# BPF_eval_R3.net
KiCad netlist of a schematic drawn in EAGLE
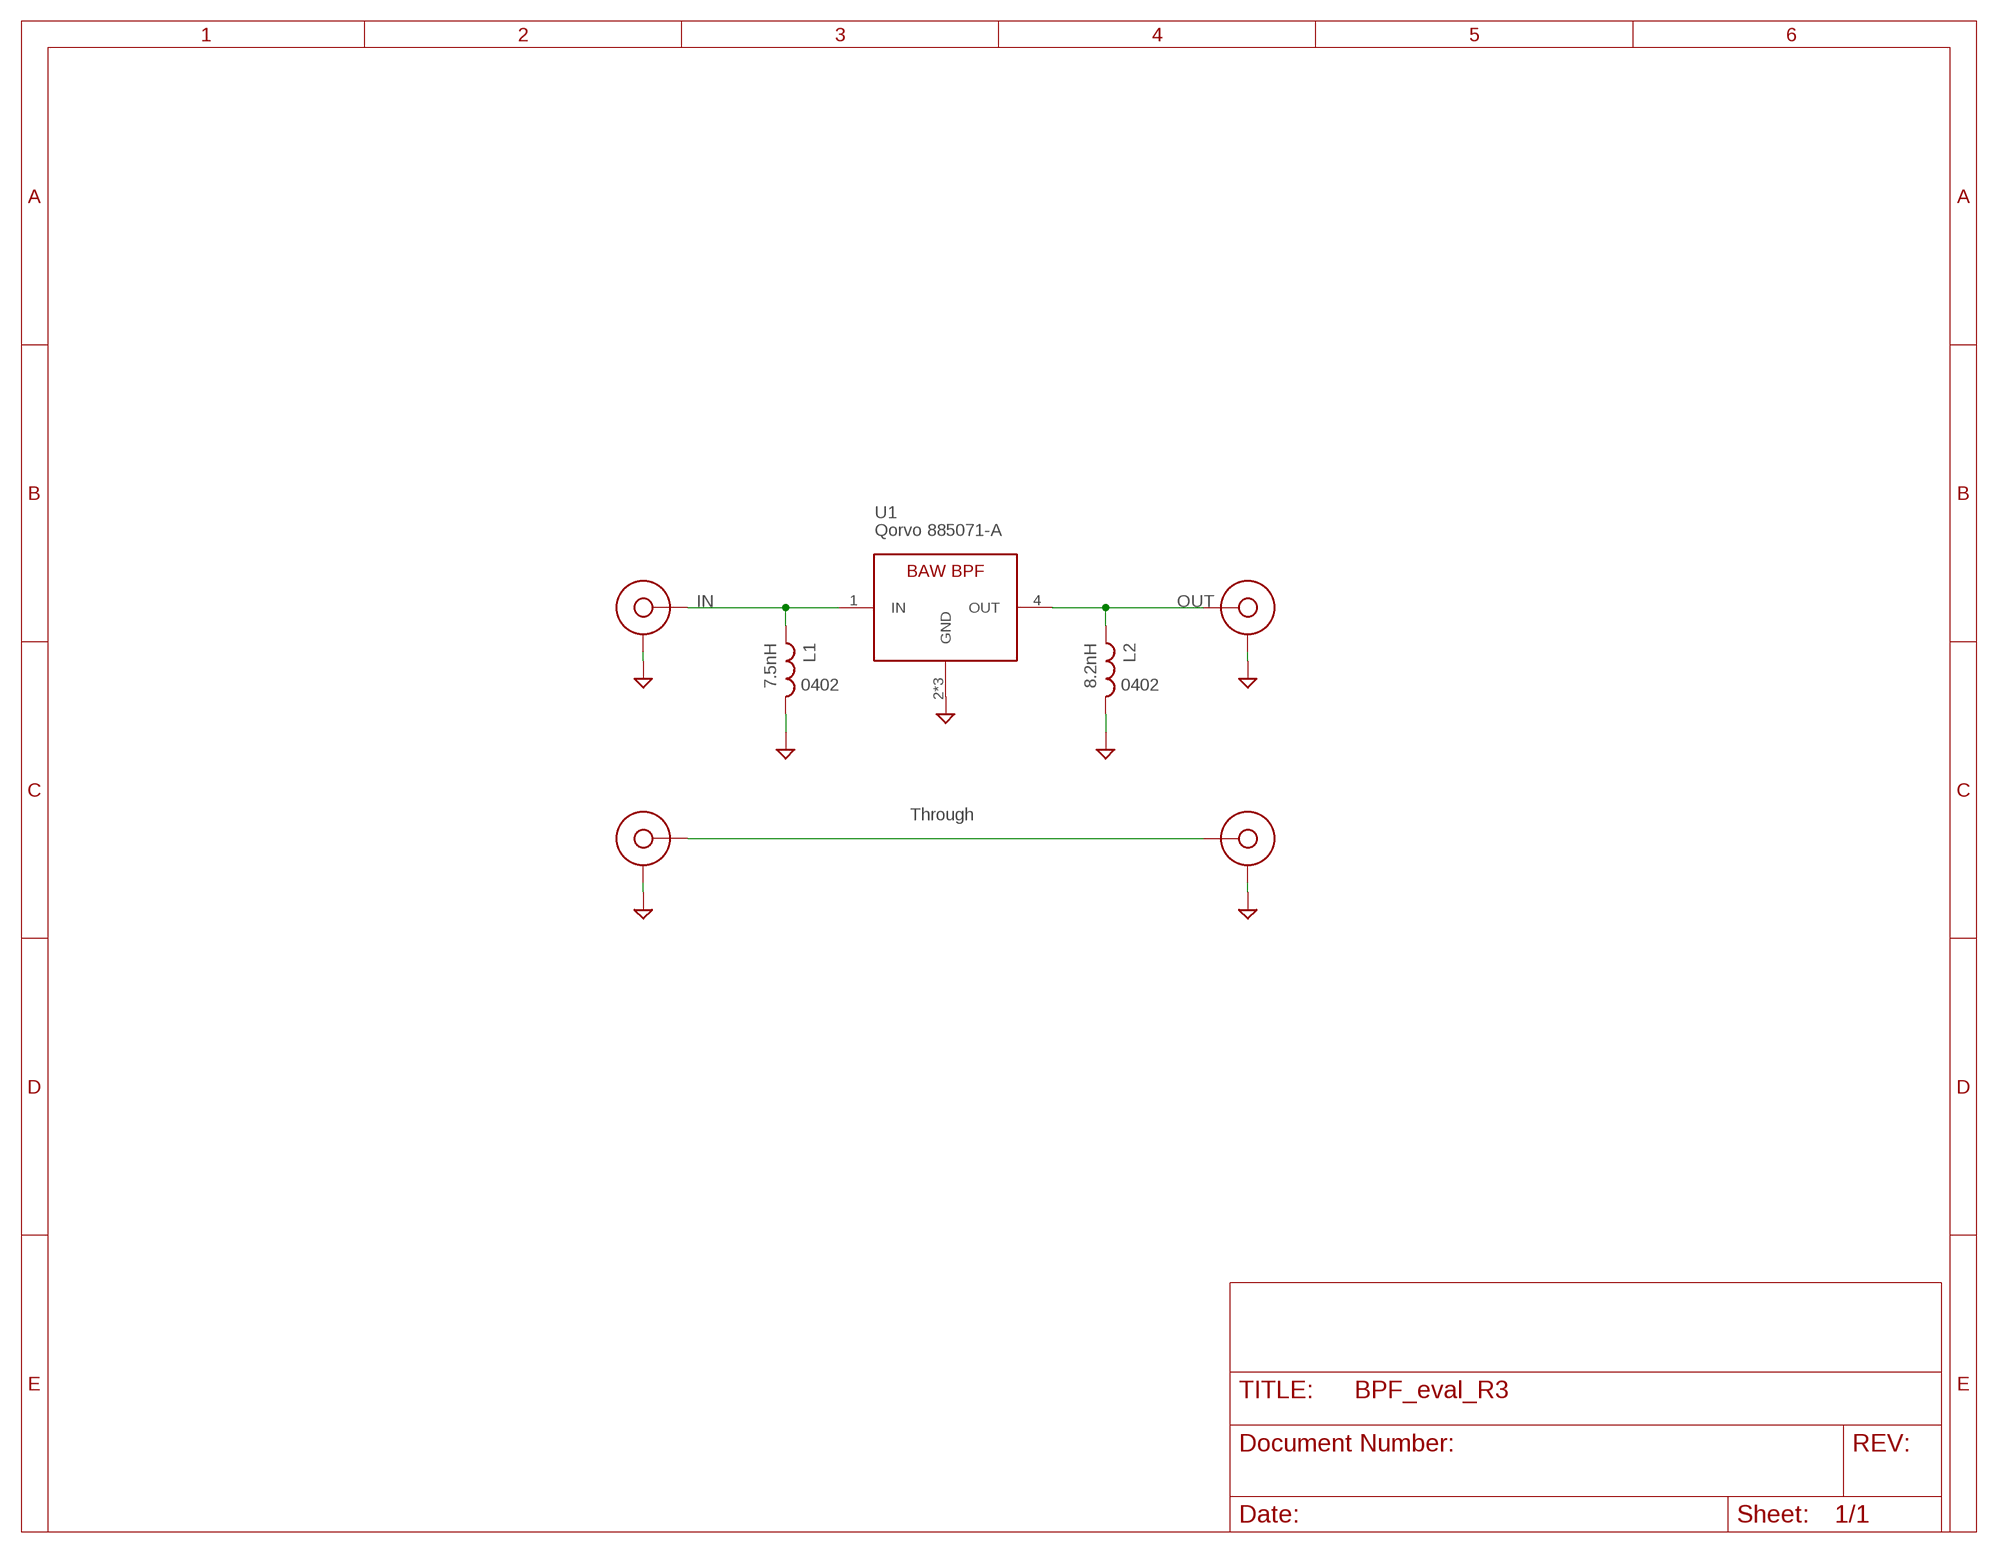
[diagram p0: schematic, sheet 1]

(export (version "E")
  (design (tool "Eeschema 10.0.6"))
  (components
    (comp (ref "CF1")
      (value "SMA-CINCH-END-FIRE")
      (footprint "eagle-import:SMAJ716-ND")
      (libsource (lib "eagle-import") (part "SMA-CINCH-END-FIRE"))
    )
    (comp (ref "CF2")
      (value "SMA-CINCH-END-FIRE")
      (footprint "eagle-import:SMAJ716-ND")
      (libsource (lib "eagle-import") (part "SMA-CINCH-END-FIRE"))
    )
    (comp (ref "CF3")
      (value "SMA-CINCH-END-FIRE")
      (footprint "eagle-import:SMAJ716-ND")
      (libsource (lib "eagle-import") (part "SMA-CINCH-END-FIRE"))
    )
    (comp (ref "CF4")
      (value "SMA-CINCH-END-FIRE")
      (footprint "eagle-import:SMAJ716-ND")
      (libsource (lib "eagle-import") (part "SMA-CINCH-END-FIRE"))
    )
    (comp (ref "L1")
      (value "7.5nH")
      (footprint "eagle-import:.0402-B-NOSILK")
      (libsource (lib "eagle-import") (part "L-US0402-B-NOSILK"))
    )
    (comp (ref "L2")
      (value "8.2nH")
      (footprint "eagle-import:.0402-B-NOSILK")
      (libsource (lib "eagle-import") (part "L-US0402-B-NOSILK"))
    )
    (comp (ref "U1")
      (value "885071-A")
      (footprint "eagle-import:FIL_B39162B9417K610")
      (libsource (lib "eagle-import") (part "885071-A"))
    )
  )
  (nets
    (net (code "1") (name "/IN") (class "Default")
      (node (ref "CF1") (pin "P$3") (pinfunction "CENTERCONDUCTOR_P$3") (pintype "bidirectional"))
      (node (ref "L1") (pin "1") (pinfunction "1_1") (pintype "passive"))
      (node (ref "U1") (pin "1") (pinfunction "IN_1") (pintype "passive"))
    )
    (net (code "2") (name "/OUT") (class "Default")
      (node (ref "CF3") (pin "P$3") (pinfunction "CENTERCONDUCTOR_P$3") (pintype "bidirectional"))
      (node (ref "L2") (pin "1") (pinfunction "1_1") (pintype "passive"))
      (node (ref "U1") (pin "4") (pinfunction "OUT_4") (pintype "passive"))
    )
    (net (code "3") (name "GND") (class "Default")
      (node (ref "CF1") (pin "GND1") (pinfunction "GND_GND1") (pintype "power_in"))
      (node (ref "CF1") (pin "GND2") (pinfunction "GND_GND2") (pintype "power_in"))
      (node (ref "CF1") (pin "GND3") (pinfunction "GND_GND3") (pintype "power_in"))
      (node (ref "CF1") (pin "GND4") (pinfunction "GND_GND4") (pintype "power_in"))
      (node (ref "CF2") (pin "GND1") (pinfunction "GND_GND1") (pintype "power_in"))
      (node (ref "CF2") (pin "GND2") (pinfunction "GND_GND2") (pintype "power_in"))
      (node (ref "CF2") (pin "GND3") (pinfunction "GND_GND3") (pintype "power_in"))
      (node (ref "CF2") (pin "GND4") (pinfunction "GND_GND4") (pintype "power_in"))
      (node (ref "CF3") (pin "GND1") (pinfunction "GND_GND1") (pintype "power_in"))
      (node (ref "CF3") (pin "GND2") (pinfunction "GND_GND2") (pintype "power_in"))
      (node (ref "CF3") (pin "GND3") (pinfunction "GND_GND3") (pintype "power_in"))
      (node (ref "CF3") (pin "GND4") (pinfunction "GND_GND4") (pintype "power_in"))
      (node (ref "CF4") (pin "GND1") (pinfunction "GND_GND1") (pintype "power_in"))
      (node (ref "CF4") (pin "GND2") (pinfunction "GND_GND2") (pintype "power_in"))
      (node (ref "CF4") (pin "GND3") (pinfunction "GND_GND3") (pintype "power_in"))
      (node (ref "CF4") (pin "GND4") (pinfunction "GND_GND4") (pintype "power_in"))
      (node (ref "L1") (pin "2") (pinfunction "2_2") (pintype "passive"))
      (node (ref "L2") (pin "2") (pinfunction "2_2") (pintype "passive"))
      (node (ref "U1") (pin "2") (pinfunction "GND_2") (pintype "power_in"))
      (node (ref "U1") (pin "3") (pinfunction "GND_3") (pintype "power_in"))
      (node (ref "U1") (pin "5") (pinfunction "GND_5") (pintype "power_in"))
    )
    (net (code "4") (name "Net-(CF2-CENTERCONDUCTOR)") (class "Default")
      (node (ref "CF2") (pin "P$3") (pinfunction "CENTERCONDUCTOR_P$3") (pintype "bidirectional"))
      (node (ref "CF4") (pin "P$3") (pinfunction "CENTERCONDUCTOR_P$3") (pintype "bidirectional"))
    )
  )
)
